# Gateway_SCH.net
KiCad netlist of a schematic drawn in Altium Designer
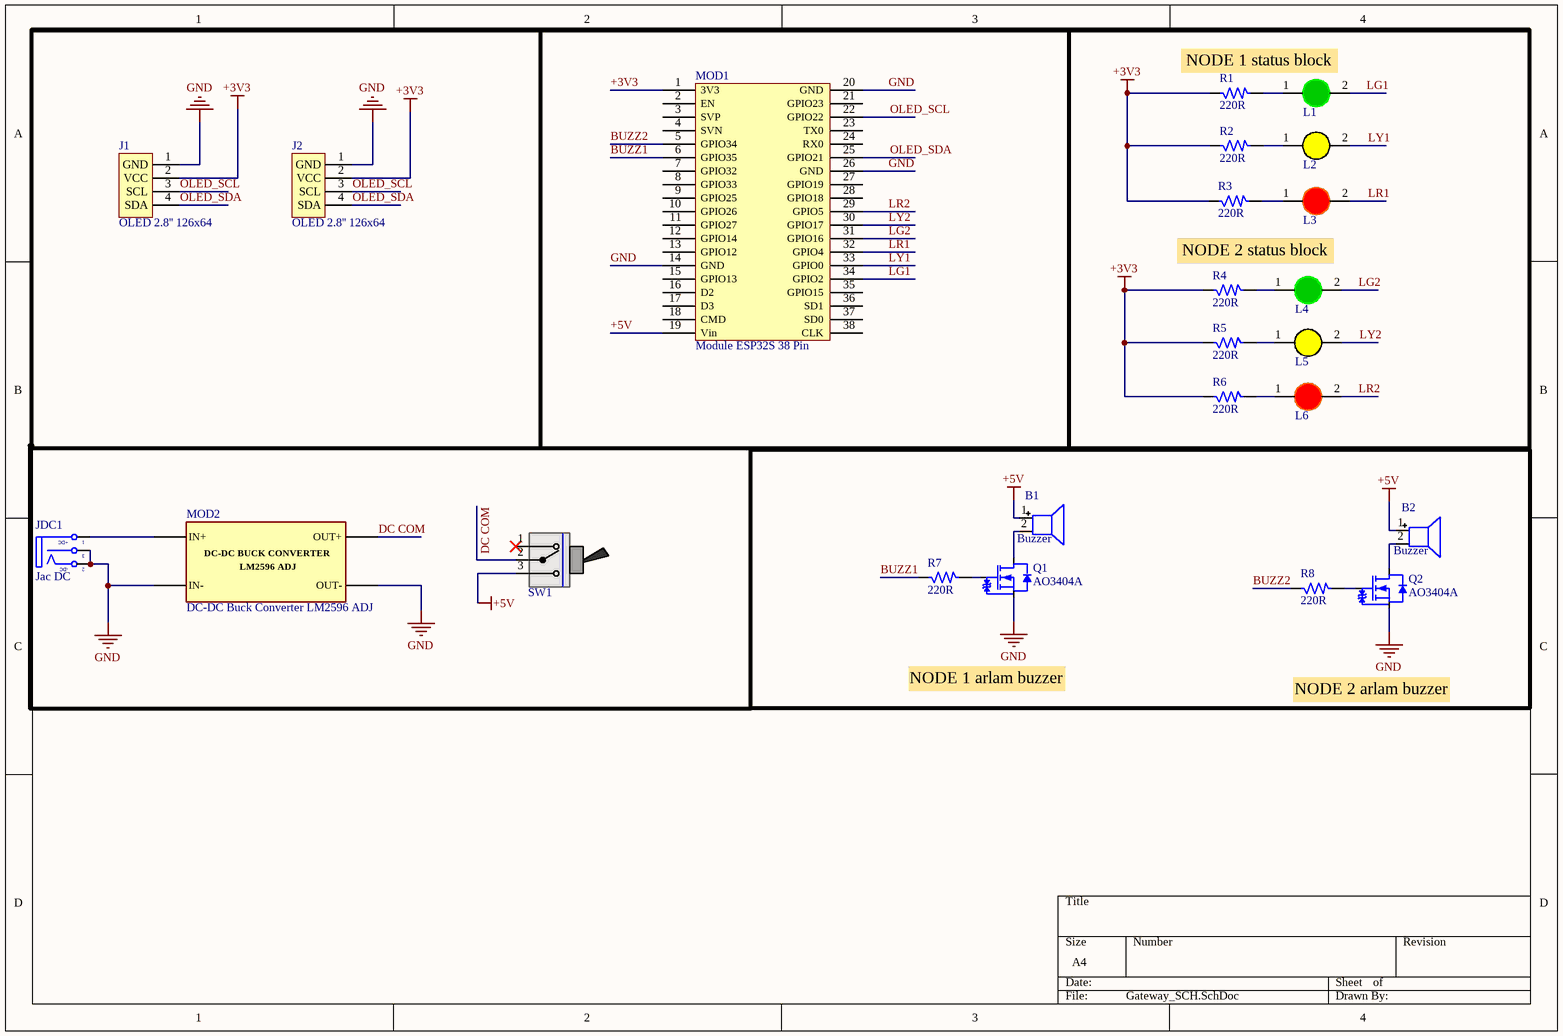
[diagram p0: Gateway_SCH.SchDoc]

(export (version "E")
  (design (tool "Eeschema 10.0.6"))
  (components
    (comp (ref "B1")
      (value "Buzzer")
      (footprint "AD_PcbLib:Coi Chip")
      (description "9.5x12mm, 7.62 pitch")
      (libsource (lib "AD_Lib") (part "Buzzer"))
    )
    (comp (ref "B2")
      (value "Buzzer")
      (footprint "AD_PcbLib:Coi Chip")
      (description "9.5x12mm, 7.62 pitch")
      (libsource (lib "AD_Lib") (part "Buzzer"))
    )
    (comp (ref "J1")
      (value "OLED 2.8'' 126x64")
      (footprint "AD_PcbLib:OLED 0.96'' 128x64")
      (fields (field (name "MANUFACTURER") "Molex") (field (name "MANUFACTURER PART NUMBER") "22-10-2061"))
      (libsource (lib "AD_Lib") (part "OLED 2.8'' 126x64"))
    )
    (comp (ref "J2")
      (value "OLED 2.8'' 126x64")
      (footprint "AD_PcbLib:OLED 0.96'' 128x64")
      (fields (field (name "MANUFACTURER") "Molex") (field (name "MANUFACTURER PART NUMBER") "22-10-2061"))
      (libsource (lib "AD_Lib") (part "OLED 2.8'' 126x64"))
    )
    (comp (ref "JDC1")
      (value "Jac DC")
      (footprint "AD_PcbLib:DC-IN")
      (description "Jac DC input")
      (libsource (lib "AD_Lib") (part "DCIN"))
    )
    (comp (ref "L1")
      (value "LED 5mm")
      (footprint "LED-5MM-Green")
      (description "Cắm")
      (libsource (lib "Altium_Lib_by_KhueNguyenCreator") (part "LED 5mm Xanh La"))
    )
    (comp (ref "L2")
      (value "LED 5mm")
      (footprint "LED-5MM-Yellow")
      (description "Cắm")
      (libsource (lib "Altium_Lib_by_KhueNguyenCreator") (part "LED 5mm Vang"))
    )
    (comp (ref "L3")
      (value "LED 5mm")
      (footprint "LED-5MM-RED")
      (description "Cắm")
      (libsource (lib "Altium_Lib_by_KhueNguyenCreator") (part "LED 5mm Do"))
    )
    (comp (ref "L4")
      (value "LED 5mm")
      (footprint "LED-5MM-Green")
      (description "Cắm")
      (libsource (lib "Altium_Lib_by_KhueNguyenCreator") (part "LED 5mm Xanh La"))
    )
    (comp (ref "L5")
      (value "LED 5mm")
      (footprint "LED-5MM-Yellow")
      (description "Cắm")
      (libsource (lib "Altium_Lib_by_KhueNguyenCreator") (part "LED 5mm Vang"))
    )
    (comp (ref "L6")
      (value "LED 5mm")
      (footprint "LED-5MM-RED")
      (description "Cắm")
      (libsource (lib "Altium_Lib_by_KhueNguyenCreator") (part "LED 5mm Do"))
    )
    (comp (ref "MOD1")
      (value "Module ESP32S 38 Pin")
      (footprint "AD_PcbLib:ESP32S MODULE 38 PIN")
      (libsource (lib "AD_Lib") (part "MOD_ESP32S_38P"))
    )
    (comp (ref "MOD2")
      (value "DC-DC Buck Converter LM2596 ADJ")
      (footprint "AD_PcbLib:Module DC-DC Buck Converter LM2596")
      (description "Input: 3-30V, Output:1.5-30V. I_out = 3A (max). Dimensions: 45x20x14mm")
      (libsource (lib "AD_Lib") (part "MOD-DC-DC_Buck_LM2596_3A"))
    )
    (comp (ref "Q1")
      (value "AO3404A")
      (footprint "SOT 23-3")
      (description "N-Channel 30V 5.8A (Ta) 1.4W (Ta) Surface Mount SOT-23-3L")
      (fields (field (name "MANUFACTURER") "International Rectifier"))
      (libsource (lib "ESTEEMPCBLIB") (part "MOSFET-N_30V-5.8A-SOT23"))
    )
    (comp (ref "Q2")
      (value "AO3404A")
      (footprint "SOT 23-3")
      (description "N-Channel 30V 5.8A (Ta) 1.4W (Ta) Surface Mount SOT-23-3L")
      (fields (field (name "MANUFACTURER") "International Rectifier"))
      (libsource (lib "ESTEEMPCBLIB") (part "MOSFET-N_30V-5.8A-SOT23"))
    )
    (comp (ref "R1")
      (value "220R")
      (footprint "AD_PcbLib:R_0805_H0.43")
      (description "Resistor")
      (libsource (lib "AD_Lib") (part "Res"))
    )
    (comp (ref "R2")
      (value "220R")
      (footprint "AD_PcbLib:R_0805_H0.43")
      (description "Resistor")
      (libsource (lib "AD_Lib") (part "Res"))
    )
    (comp (ref "R3")
      (value "220R")
      (footprint "AD_PcbLib:R_0805_H0.43")
      (description "Resistor")
      (libsource (lib "AD_Lib") (part "Res"))
    )
    (comp (ref "R4")
      (value "220R")
      (footprint "AD_PcbLib:R_0805_H0.43")
      (description "Resistor")
      (libsource (lib "AD_Lib") (part "Res"))
    )
    (comp (ref "R5")
      (value "220R")
      (footprint "AD_PcbLib:R_0805_H0.43")
      (description "Resistor")
      (libsource (lib "AD_Lib") (part "Res"))
    )
    (comp (ref "R6")
      (value "220R")
      (footprint "AD_PcbLib:R_0805_H0.43")
      (description "Resistor")
      (libsource (lib "AD_Lib") (part "Res"))
    )
    (comp (ref "R7")
      (value "220R")
      (footprint "AD_PcbLib:R_0805_H0.43")
      (description "Resistor")
      (libsource (lib "AD_Lib") (part "Res"))
    )
    (comp (ref "R8")
      (value "220R")
      (footprint "AD_PcbLib:R_0805_H0.43")
      (description "Resistor")
      (libsource (lib "AD_Lib") (part "Res"))
    )
    (comp (ref "SW1")
      (value "SW_Toggle_MST-103")
      (footprint "AD_PcbLib:TOGGLE SWITCH MTS-103")
      (description "SWITCH TOGGLE")
      (fields (field (name "MANF") "Apem") (field (name "MANF_PART#") "MHSS1105"))
      (libsource (lib "AD_Lib") (part "SW_Toggle_MST-103"))
    )
  )
  (nets
    (net (code "1") (name "+3V3") (class "Default")
      (node (ref "J1") (pin "2") (pinfunction "VCC_2") (pintype "passive"))
      (node (ref "J2") (pin "2") (pinfunction "VCC_2") (pintype "passive"))
      (node (ref "MOD1") (pin "1") (pinfunction "3V3_1") (pintype "passive"))
      (node (ref "R1") (pin "1") (pinfunction "1_1") (pintype "passive"))
      (node (ref "R2") (pin "1") (pinfunction "1_1") (pintype "passive"))
      (node (ref "R3") (pin "1") (pinfunction "1_1") (pintype "passive"))
      (node (ref "R4") (pin "1") (pinfunction "1_1") (pintype "passive"))
      (node (ref "R5") (pin "1") (pinfunction "1_1") (pintype "passive"))
      (node (ref "R6") (pin "1") (pinfunction "1_1") (pintype "passive"))
    )
    (net (code "2") (name "+5V") (class "Default")
      (node (ref "B1") (pin "1") (pinfunction "+_1") (pintype "passive"))
      (node (ref "B2") (pin "1") (pinfunction "+_1") (pintype "passive"))
      (node (ref "MOD1") (pin "19") (pinfunction "Vin_19") (pintype "passive"))
      (node (ref "SW1") (pin "3") (pinfunction "3_3") (pintype "passive"))
    )
    (net (code "3") (name "/BUZZ1") (class "Default")
      (node (ref "MOD1") (pin "6") (pinfunction "GPIO35_6") (pintype "passive"))
      (node (ref "R7") (pin "1") (pinfunction "1_1") (pintype "passive"))
    )
    (net (code "4") (name "/BUZZ2") (class "Default")
      (node (ref "MOD1") (pin "5") (pinfunction "GPIO34_5") (pintype "passive"))
      (node (ref "R8") (pin "1") (pinfunction "1_1") (pintype "passive"))
    )
    (net (code "5") (name "/DC COM") (class "Default")
      (node (ref "MOD2") (pin "3") (pinfunction "OUT+_3") (pintype "passive"))
      (node (ref "SW1") (pin "2") (pinfunction "2_2") (pintype "passive"))
    )
    (net (code "6") (name "/LG1") (class "Default")
      (node (ref "L1") (pin "2") (pinfunction "K_2") (pintype "passive"))
      (node (ref "MOD1") (pin "34") (pinfunction "GPIO2_34") (pintype "passive"))
    )
    (net (code "7") (name "/LG2") (class "Default")
      (node (ref "L4") (pin "2") (pinfunction "K_2") (pintype "passive"))
      (node (ref "MOD1") (pin "31") (pinfunction "GPIO16_31") (pintype "passive"))
    )
    (net (code "8") (name "/LR1") (class "Default")
      (node (ref "L3") (pin "2") (pinfunction "K_2") (pintype "passive"))
      (node (ref "MOD1") (pin "32") (pinfunction "GPIO4_32") (pintype "passive"))
    )
    (net (code "9") (name "/LR2") (class "Default")
      (node (ref "L6") (pin "2") (pinfunction "K_2") (pintype "passive"))
      (node (ref "MOD1") (pin "29") (pinfunction "GPIO5_29") (pintype "passive"))
    )
    (net (code "10") (name "/LY1") (class "Default")
      (node (ref "L2") (pin "2") (pinfunction "K_2") (pintype "passive"))
      (node (ref "MOD1") (pin "33") (pinfunction "GPIO0_33") (pintype "passive"))
    )
    (net (code "11") (name "/LY2") (class "Default")
      (node (ref "L5") (pin "2") (pinfunction "K_2") (pintype "passive"))
      (node (ref "MOD1") (pin "30") (pinfunction "GPIO17_30") (pintype "passive"))
    )
    (net (code "12") (name "/OLED_SCL") (class "Default")
      (node (ref "J1") (pin "3") (pinfunction "SCL_3") (pintype "passive"))
      (node (ref "J2") (pin "3") (pinfunction "SCL_3") (pintype "passive"))
      (node (ref "MOD1") (pin "22") (pinfunction "GPIO22_22") (pintype "passive"))
    )
    (net (code "13") (name "/OLED_SDA") (class "Default")
      (node (ref "J1") (pin "4") (pinfunction "SDA_4") (pintype "passive"))
      (node (ref "J2") (pin "4") (pinfunction "SDA_4") (pintype "passive"))
      (node (ref "MOD1") (pin "25") (pinfunction "GPIO21_25") (pintype "passive"))
    )
    (net (code "14") (name "GND") (class "Default")
      (node (ref "J1") (pin "1") (pinfunction "GND_1") (pintype "passive"))
      (node (ref "J2") (pin "1") (pinfunction "GND_1") (pintype "passive"))
      (node (ref "JDC1") (pin "2") (pinfunction "TN_2") (pintype "passive"))
      (node (ref "JDC1") (pin "3") (pinfunction "S_3") (pintype "power_in"))
      (node (ref "MOD1") (pin "14") (pinfunction "GND_14") (pintype "passive"))
      (node (ref "MOD1") (pin "20") (pinfunction "GND_20") (pintype "passive"))
      (node (ref "MOD1") (pin "26") (pinfunction "GND_26") (pintype "passive"))
      (node (ref "MOD2") (pin "2") (pinfunction "IN-_2") (pintype "passive"))
      (node (ref "MOD2") (pin "4") (pinfunction "OUT-_4") (pintype "passive"))
      (node (ref "Q1") (pin "2") (pinfunction "S_2") (pintype "passive"))
      (node (ref "Q2") (pin "2") (pinfunction "S_2") (pintype "passive"))
    )
    (net (code "15") (name "Net-(JDC1-T)") (class "Default")
      (node (ref "JDC1") (pin "1") (pinfunction "T_1") (pintype "passive"))
      (node (ref "MOD2") (pin "1") (pinfunction "IN+_1") (pintype "passive"))
    )
    (net (code "16") (name "Net-(L1-A)") (class "Default")
      (node (ref "L1") (pin "1") (pinfunction "A_1") (pintype "passive"))
      (node (ref "R1") (pin "2") (pinfunction "2_2") (pintype "passive"))
    )
    (net (code "17") (name "Net-(L2-A)") (class "Default")
      (node (ref "L2") (pin "1") (pinfunction "A_1") (pintype "passive"))
      (node (ref "R2") (pin "2") (pinfunction "2_2") (pintype "passive"))
    )
    (net (code "18") (name "Net-(L3-A)") (class "Default")
      (node (ref "L3") (pin "1") (pinfunction "A_1") (pintype "passive"))
      (node (ref "R3") (pin "2") (pinfunction "2_2") (pintype "passive"))
    )
    (net (code "19") (name "Net-(L4-A)") (class "Default")
      (node (ref "L4") (pin "1") (pinfunction "A_1") (pintype "passive"))
      (node (ref "R4") (pin "2") (pinfunction "2_2") (pintype "passive"))
    )
    (net (code "20") (name "Net-(L5-A)") (class "Default")
      (node (ref "L5") (pin "1") (pinfunction "A_1") (pintype "passive"))
      (node (ref "R5") (pin "2") (pinfunction "2_2") (pintype "passive"))
    )
    (net (code "21") (name "Net-(L6-A)") (class "Default")
      (node (ref "L6") (pin "1") (pinfunction "A_1") (pintype "passive"))
      (node (ref "R6") (pin "2") (pinfunction "2_2") (pintype "passive"))
    )
    (net (code "22") (name "Net-(Q1-D)") (class "Default")
      (node (ref "B1") (pin "2") (pinfunction "2_2") (pintype "passive"))
      (node (ref "Q1") (pin "3") (pinfunction "D_3") (pintype "passive"))
    )
    (net (code "23") (name "Net-(Q1-G)") (class "Default")
      (node (ref "Q1") (pin "1") (pinfunction "G_1") (pintype "passive"))
      (node (ref "R7") (pin "2") (pinfunction "2_2") (pintype "passive"))
    )
    (net (code "24") (name "Net-(Q2-D)") (class "Default")
      (node (ref "B2") (pin "2") (pinfunction "2_2") (pintype "passive"))
      (node (ref "Q2") (pin "3") (pinfunction "D_3") (pintype "passive"))
    )
    (net (code "25") (name "Net-(Q2-G)") (class "Default")
      (node (ref "Q2") (pin "1") (pinfunction "G_1") (pintype "passive"))
      (node (ref "R8") (pin "2") (pinfunction "2_2") (pintype "passive"))
    )
    (net (code "26") (name "unconnected-(MOD1-CLK-Pad38)") (class "Default")
      (node (ref "MOD1") (pin "38") (pinfunction "CLK_38") (pintype "passive"))
    )
    (net (code "27") (name "unconnected-(MOD1-CMD-Pad18)") (class "Default")
      (node (ref "MOD1") (pin "18") (pinfunction "CMD_18") (pintype "passive"))
    )
    (net (code "28") (name "unconnected-(MOD1-D2-Pad16)") (class "Default")
      (node (ref "MOD1") (pin "16") (pinfunction "D2_16") (pintype "passive"))
    )
    (net (code "29") (name "unconnected-(MOD1-D3-Pad17)") (class "Default")
      (node (ref "MOD1") (pin "17") (pinfunction "D3_17") (pintype "passive"))
    )
    (net (code "30") (name "unconnected-(MOD1-EN-Pad2)") (class "Default")
      (node (ref "MOD1") (pin "2") (pinfunction "EN_2") (pintype "passive"))
    )
    (net (code "31") (name "unconnected-(MOD1-GPIO12-Pad13)") (class "Default")
      (node (ref "MOD1") (pin "13") (pinfunction "GPIO12_13") (pintype "passive"))
    )
    (net (code "32") (name "unconnected-(MOD1-GPIO13-Pad15)") (class "Default")
      (node (ref "MOD1") (pin "15") (pinfunction "GPIO13_15") (pintype "passive"))
    )
    (net (code "33") (name "unconnected-(MOD1-GPIO14-Pad12)") (class "Default")
      (node (ref "MOD1") (pin "12") (pinfunction "GPIO14_12") (pintype "passive"))
    )
    (net (code "34") (name "unconnected-(MOD1-GPIO15-Pad35)") (class "Default")
      (node (ref "MOD1") (pin "35") (pinfunction "GPIO15_35") (pintype "passive"))
    )
    (net (code "35") (name "unconnected-(MOD1-GPIO18-Pad28)") (class "Default")
      (node (ref "MOD1") (pin "28") (pinfunction "GPIO18_28") (pintype "passive"))
    )
    (net (code "36") (name "unconnected-(MOD1-GPIO19-Pad27)") (class "Default")
      (node (ref "MOD1") (pin "27") (pinfunction "GPIO19_27") (pintype "passive"))
    )
    (net (code "37") (name "unconnected-(MOD1-GPIO23-Pad21)") (class "Default")
      (node (ref "MOD1") (pin "21") (pinfunction "GPIO23_21") (pintype "passive"))
    )
    (net (code "38") (name "unconnected-(MOD1-GPIO25-Pad9)") (class "Default")
      (node (ref "MOD1") (pin "9") (pinfunction "GPIO25_9") (pintype "passive"))
    )
    (net (code "39") (name "unconnected-(MOD1-GPIO26-Pad10)") (class "Default")
      (node (ref "MOD1") (pin "10") (pinfunction "GPIO26_10") (pintype "passive"))
    )
    (net (code "40") (name "unconnected-(MOD1-GPIO27-Pad11)") (class "Default")
      (node (ref "MOD1") (pin "11") (pinfunction "GPIO27_11") (pintype "passive"))
    )
    (net (code "41") (name "unconnected-(MOD1-GPIO32-Pad7)") (class "Default")
      (node (ref "MOD1") (pin "7") (pinfunction "GPIO32_7") (pintype "passive"))
    )
    (net (code "42") (name "unconnected-(MOD1-GPIO33-Pad8)") (class "Default")
      (node (ref "MOD1") (pin "8") (pinfunction "GPIO33_8") (pintype "passive"))
    )
    (net (code "43") (name "unconnected-(MOD1-RX0-Pad24)") (class "Default")
      (node (ref "MOD1") (pin "24") (pinfunction "RX0_24") (pintype "passive"))
    )
    (net (code "44") (name "unconnected-(MOD1-SD0-Pad37)") (class "Default")
      (node (ref "MOD1") (pin "37") (pinfunction "SD0_37") (pintype "passive"))
    )
    (net (code "45") (name "unconnected-(MOD1-SD1-Pad36)") (class "Default")
      (node (ref "MOD1") (pin "36") (pinfunction "SD1_36") (pintype "passive"))
    )
    (net (code "46") (name "unconnected-(MOD1-SVN-Pad4)") (class "Default")
      (node (ref "MOD1") (pin "4") (pinfunction "SVN_4") (pintype "passive"))
    )
    (net (code "47") (name "unconnected-(MOD1-SVP-Pad3)") (class "Default")
      (node (ref "MOD1") (pin "3") (pinfunction "SVP_3") (pintype "passive"))
    )
    (net (code "48") (name "unconnected-(MOD1-TX0-Pad23)") (class "Default")
      (node (ref "MOD1") (pin "23") (pinfunction "TX0_23") (pintype "passive"))
    )
    (net (code "49") (name "unconnected-(SW1-Pad1)") (class "Default")
      (node (ref "SW1") (pin "1") (pinfunction "1_1") (pintype "passive+no_connect"))
    )
  )
)
